# UAV2_0_DOC.net
KiCad netlist of a schematic drawn in Altium Designer
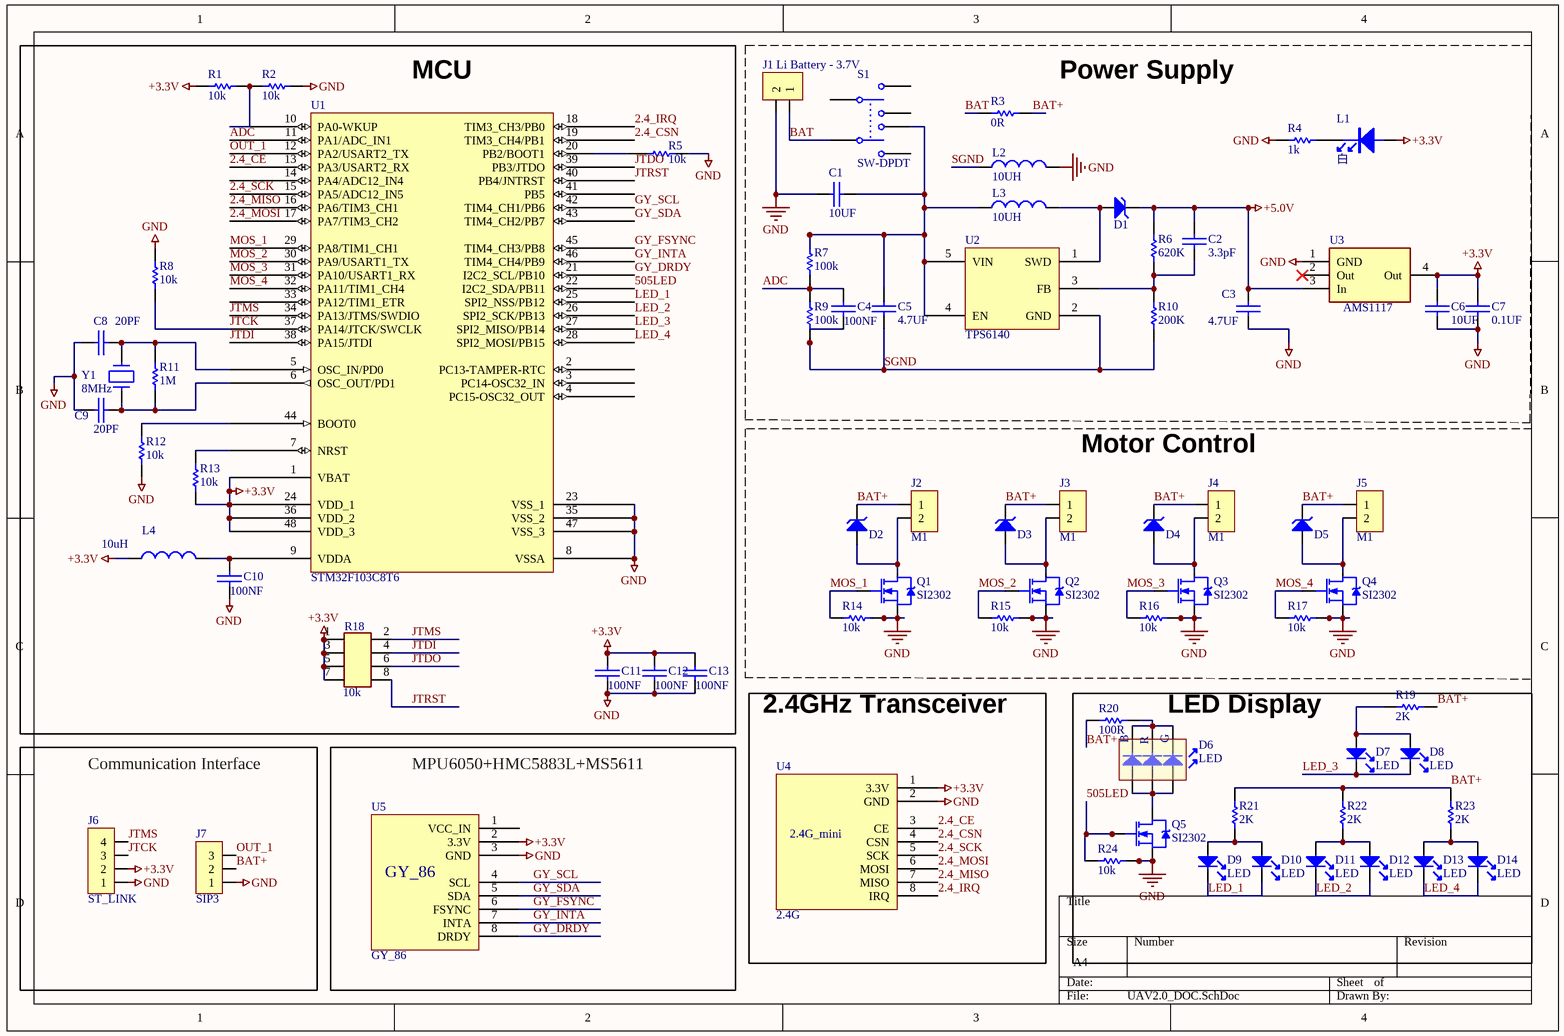
[diagram p0: UAV2.0_DOC.SchDoc]

(export (version "E")
  (design (tool "Eeschema 10.0.6"))
  (components
    (comp (ref "C1")
      (value "10UF")
      (footprint "1206C")
      (description "Capacitor/小容量电容")
      (libsource (lib "狗尾巴草设计室") (part "CAP"))
    )
    (comp (ref "C2")
      (value "3.3pF")
      (footprint "0805C")
      (description "Capacitor/小容量电容")
      (libsource (lib "狗尾巴草设计室") (part "CAP"))
    )
    (comp (ref "C3")
      (value "4.7UF")
      (footprint "1206C")
      (description "Capacitor/小容量电容")
      (libsource (lib "狗尾巴草设计室") (part "CAP"))
    )
    (comp (ref "C4")
      (value "100NF")
      (footprint "0805C")
      (description "Capacitor/小容量电容")
      (libsource (lib "狗尾巴草设计室") (part "CAP"))
    )
    (comp (ref "C5")
      (value "4.7UF")
      (footprint "0805C")
      (description "Capacitor/小容量电容")
      (libsource (lib "狗尾巴草设计室") (part "CAP"))
    )
    (comp (ref "C6")
      (value "10UF")
      (footprint "1206C")
      (description "Capacitor/小容量电容")
      (libsource (lib "狗尾巴草设计室") (part "CAP"))
    )
    (comp (ref "C7")
      (value "0.1UF")
      (footprint "0805C")
      (description "Capacitor/小容量电容")
      (libsource (lib "狗尾巴草设计室") (part "CAP"))
    )
    (comp (ref "C8")
      (value "20PF")
      (footprint "0805C")
      (description "Capacitor/小容量电容")
      (libsource (lib "狗尾巴草设计室") (part "CAP"))
    )
    (comp (ref "C9")
      (value "20PF")
      (footprint "0805C")
      (description "Capacitor/小容量电容")
      (libsource (lib "狗尾巴草设计室") (part "CAP"))
    )
    (comp (ref "C10")
      (value "100NF")
      (footprint "0805C")
      (description "Capacitor/小容量电容")
      (libsource (lib "狗尾巴草设计室") (part "CAP"))
    )
    (comp (ref "C11")
      (value "100NF")
      (footprint "0805C")
      (description "Capacitor/小容量电容")
      (libsource (lib "狗尾巴草设计室") (part "CAP"))
    )
    (comp (ref "C12")
      (value "100NF")
      (footprint "0805C")
      (description "Capacitor/小容量电容")
      (libsource (lib "狗尾巴草设计室") (part "CAP"))
    )
    (comp (ref "C13")
      (value "100NF")
      (footprint "0805C")
      (description "Capacitor/小容量电容")
      (libsource (lib "狗尾巴草设计室") (part "CAP"))
    )
    (comp (ref "D1")
      (value "DIODE-S")
      (footprint "C_SMA_3216")
      (description "SCHOTTKEY")
      (libsource (lib "狗尾巴草设计室") (part "DIODE-S"))
    )
    (comp (ref "D2")
      (value "DIODE-S")
      (footprint "C_SMA_3216")
      (description "SCHOTTKEY")
      (libsource (lib "狗尾巴草设计室") (part "DIODE-S"))
    )
    (comp (ref "D3")
      (value "DIODE-S")
      (footprint "C_SMA_3216")
      (description "SCHOTTKEY")
      (libsource (lib "狗尾巴草设计室") (part "DIODE-S"))
    )
    (comp (ref "D4")
      (value "DIODE-S")
      (footprint "C_SMA_3216")
      (description "SCHOTTKEY")
      (libsource (lib "狗尾巴草设计室") (part "DIODE-S"))
    )
    (comp (ref "D5")
      (value "DIODE-S")
      (footprint "C_SMA_3216")
      (description "SCHOTTKEY")
      (libsource (lib "狗尾巴草设计室") (part "DIODE-S"))
    )
    (comp (ref "D6") (value "LED") (footprint "LED5050_RGB") (libsource (lib "狗尾巴草设计室") (part "LED_5050RGB")))
    (comp (ref "D7") (value "LED") (footprint "0805D") (libsource (lib "狗尾巴草设计室") (part "LED")))
    (comp (ref "D8") (value "LED") (footprint "0805D") (libsource (lib "狗尾巴草设计室") (part "LED")))
    (comp (ref "D9") (value "LED") (footprint "0805D") (libsource (lib "狗尾巴草设计室") (part "LED")))
    (comp (ref "D10") (value "LED") (footprint "0805D") (libsource (lib "狗尾巴草设计室") (part "LED")))
    (comp (ref "D11") (value "LED") (footprint "0805D") (libsource (lib "狗尾巴草设计室") (part "LED")))
    (comp (ref "D12") (value "LED") (footprint "0805D") (libsource (lib "狗尾巴草设计室") (part "LED")))
    (comp (ref "D13") (value "LED") (footprint "0805D") (libsource (lib "狗尾巴草设计室") (part "LED")))
    (comp (ref "D14") (value "LED") (footprint "0805D") (libsource (lib "狗尾巴草设计室") (part "LED")))
    (comp (ref "J1")
      (value "Li Battery - 3.7V")
      (footprint "P2_2.0-2")
      (libsource (lib "狗尾巴草设计室") (part "SIP2"))
    )
    (comp (ref "J2") (value "M1") (footprint "P2_2.0-1") (libsource (lib "狗尾巴草设计室") (part "SIP2")))
    (comp (ref "J3") (value "M1") (footprint "P2_2.0-1") (libsource (lib "狗尾巴草设计室") (part "SIP2")))
    (comp (ref "J4") (value "M1") (footprint "P2_2.0-1") (libsource (lib "狗尾巴草设计室") (part "SIP2")))
    (comp (ref "J5") (value "M1") (footprint "P2_2.0-1") (libsource (lib "狗尾巴草设计室") (part "SIP2")))
    (comp (ref "J6") (value "ST_LINK") (footprint "P4_2.54-1") (libsource (lib "狗尾巴草设计室") (part "SIP4")))
    (comp (ref "J7") (value "SIP3") (footprint "PC_3") (libsource (lib "狗尾巴草设计室") (part "SIP3")))
    (comp (ref "L1") (value "白") (footprint "D0805") (libsource (lib "CommonSCH") (part "LED")))
    (comp (ref "L2") (value "10UH") (footprint "1206") (libsource (lib "狗尾巴草设计室") (part "L")))
    (comp (ref "L3") (value "10UH") (footprint "1206") (libsource (lib "狗尾巴草设计室") (part "L")))
    (comp (ref "L4")
      (value "INDUCTOR")
      (footprint "R0805")
      (fields (field (name "VAL") "10uH"))
      (libsource (lib "SCH") (part "INDUCTOR"))
    )
    (comp (ref "Q1")
      (value "SI2302")
      (footprint "PCB四轴lib_pcb:SI2302")
      (libsource (lib "BK四轴1.0_lib") (part "SI2302"))
    )
    (comp (ref "Q2")
      (value "SI2302")
      (footprint "PCB四轴lib_pcb:SI2302")
      (libsource (lib "BK四轴1.0_lib") (part "SI2302"))
    )
    (comp (ref "Q3")
      (value "SI2302")
      (footprint "PCB四轴lib_pcb:SI2302")
      (libsource (lib "BK四轴1.0_lib") (part "SI2302"))
    )
    (comp (ref "Q4")
      (value "SI2302")
      (footprint "PCB四轴lib_pcb:SI2302")
      (libsource (lib "BK四轴1.0_lib") (part "SI2302"))
    )
    (comp (ref "Q5")
      (value "SI2302")
      (footprint "PCB四轴lib_pcb:SI2302")
      (libsource (lib "BK四轴1.0_lib") (part "SI2302"))
    )
    (comp (ref "R1")
      (value "RES")
      (footprint "R0805")
      (description "Semiconductor Resistor")
      (fields (field (name "VAL") "10k") (field (name "PUBLISHER") "*"))
      (libsource (lib "SCH") (part "RES"))
    )
    (comp (ref "R2")
      (value "RES")
      (footprint "R0805")
      (description "Semiconductor Resistor")
      (fields (field (name "VAL") "10k") (field (name "PUBLISHER") "*"))
      (libsource (lib "SCH") (part "RES"))
    )
    (comp (ref "R3") (value "0R") (footprint "2512R - duplicate") (libsource (lib "狗尾巴草设计室") (part "Res_1")))
    (comp (ref "R4")
      (value "1k")
      (footprint "R0805")
      (description "Resistor")
      (fields (field (name "Comment") "Res1") (field (name "PUBLISHER") "Altium Limited"))
      (libsource (lib "SCHLIB1") (part "Res1"))
    )
    (comp (ref "R5")
      (value "RES")
      (footprint "R0805")
      (description "Semiconductor Resistor")
      (fields (field (name "VAL") "10k") (field (name "PUBLISHER") "*"))
      (libsource (lib "SCH") (part "RES"))
    )
    (comp (ref "R6") (value "620K") (footprint "0805R") (libsource (lib "狗尾巴草设计室") (part "Res")))
    (comp (ref "R7")
      (value "RES")
      (footprint "R0805")
      (description "Semiconductor Resistor")
      (fields (field (name "VAL") "100k") (field (name "PUBLISHER") "*"))
      (libsource (lib "SCH") (part "RES"))
    )
    (comp (ref "R8")
      (value "RES")
      (footprint "R0805")
      (description "Semiconductor Resistor")
      (fields (field (name "VAL") "10k") (field (name "PUBLISHER") "*"))
      (libsource (lib "SCH") (part "RES"))
    )
    (comp (ref "R9")
      (value "RES")
      (footprint "R0805")
      (description "Semiconductor Resistor")
      (fields (field (name "VAL") "100k") (field (name "PUBLISHER") "*"))
      (libsource (lib "SCH") (part "RES"))
    )
    (comp (ref "R10") (value "200K") (footprint "0805R") (libsource (lib "狗尾巴草设计室") (part "Res")))
    (comp (ref "R11")
      (value "RES")
      (footprint "R0805")
      (description "Semiconductor Resistor")
      (fields (field (name "VAL") "1M") (field (name "PUBLISHER") "*"))
      (libsource (lib "SCH") (part "RES"))
    )
    (comp (ref "R12")
      (value "RES")
      (footprint "R0805")
      (description "Semiconductor Resistor")
      (fields (field (name "VAL") "10k") (field (name "PUBLISHER") "*"))
      (libsource (lib "SCH") (part "RES"))
    )
    (comp (ref "R13")
      (value "RES")
      (footprint "R0805")
      (description "Semiconductor Resistor")
      (fields (field (name "VAL") "10k") (field (name "PUBLISHER") "*"))
      (libsource (lib "SCH") (part "RES"))
    )
    (comp (ref "R14")
      (value "RES")
      (footprint "R0805")
      (description "Semiconductor Resistor")
      (fields (field (name "VAL") "10k") (field (name "PUBLISHER") "*"))
      (libsource (lib "SCH") (part "RES"))
    )
    (comp (ref "R15")
      (value "RES")
      (footprint "R0805")
      (description "Semiconductor Resistor")
      (fields (field (name "VAL") "10k") (field (name "PUBLISHER") "*"))
      (libsource (lib "SCH") (part "RES"))
    )
    (comp (ref "R16")
      (value "RES")
      (footprint "R0805")
      (description "Semiconductor Resistor")
      (fields (field (name "VAL") "10k") (field (name "PUBLISHER") "*"))
      (libsource (lib "SCH") (part "RES"))
    )
    (comp (ref "R17")
      (value "RES")
      (footprint "R0805")
      (description "Semiconductor Resistor")
      (fields (field (name "VAL") "10k") (field (name "PUBLISHER") "*"))
      (libsource (lib "SCH") (part "RES"))
    )
    (comp (ref "R18")
      (value "10k")
      (footprint "8P4R_0603")
      (description "8P4R_0603")
      (libsource (lib "SCH") (part "8P4R_0603"))
    )
    (comp (ref "R19")
      (value "RES")
      (footprint "R0805")
      (description "Semiconductor Resistor")
      (fields (field (name "VAL") "2K") (field (name "PUBLISHER") "*"))
      (libsource (lib "SCH") (part "RES"))
    )
    (comp (ref "R20") (value "100R") (footprint "0805R") (libsource (lib "狗尾巴草设计室") (part "Res")))
    (comp (ref "R21")
      (value "RES")
      (footprint "R0805")
      (description "Semiconductor Resistor")
      (fields (field (name "VAL") "2K") (field (name "PUBLISHER") "*"))
      (libsource (lib "SCH") (part "RES"))
    )
    (comp (ref "R22")
      (value "RES")
      (footprint "R0805")
      (description "Semiconductor Resistor")
      (fields (field (name "VAL") "2K") (field (name "PUBLISHER") "*"))
      (libsource (lib "SCH") (part "RES"))
    )
    (comp (ref "R23")
      (value "RES")
      (footprint "R0805")
      (description "Semiconductor Resistor")
      (fields (field (name "VAL") "2K") (field (name "PUBLISHER") "*"))
      (libsource (lib "SCH") (part "RES"))
    )
    (comp (ref "R24")
      (value "RES")
      (footprint "R0805")
      (description "Semiconductor Resistor")
      (fields (field (name "VAL") "10k") (field (name "PUBLISHER") "*"))
      (libsource (lib "SCH") (part "RES"))
    )
    (comp (ref "S1")
      (value "SW-DPDT")
      (footprint "KEY_KFT7.0")
      (description "Double-Pole, Double-Throw Switch")
      (fields (field (name "PUBLISHER") "Altium Limited"))
      (libsource (lib "Miscellaneous Devices") (part "SW-DPDT"))
    )
    (comp (ref "U1")
      (value "STM32F103C8T6")
      (footprint "LQFP48_N")
      (description "STM32 ARM-based 32-bit MCU with 64 Kbytes Flash, 48-pin LQFP, Industrial Temperature")
      (fields (field (name "PUBLISHER") "*"))
      (libsource (lib "ZF_library") (part "STM32F103C8T6"))
    )
    (comp (ref "U2")
      (value "TPS6140")
      (footprint "SOT-23-5")
      (libsource (lib "BK四轴1.0_lib") (part "TPS6140"))
    )
    (comp (ref "U3")
      (value "AMS1117")
      (footprint "ZZ311")
      (description "Header, 2-Pin")
      (fields (field (name "PUBLISHER") "*"))
      (libsource (lib "CommonSCH") (part "AMS1117"))
    )
    (comp (ref "U4")
      (value "2.4G")
      (footprint "2.4G_mini")
      (libsource (lib "BK四轴1.0_lib") (part "2.4G_mini"))
    )
    (comp (ref "U5") (value "GY_86") (footprint "P8_2.54-1") (libsource (lib "BK四轴1.0_lib") (part "GY_86")))
    (comp (ref "Y1")
      (value "CRYSTAL1")
      (footprint "Y2")
      (fields (field (name "VAL") "8MHz"))
      (libsource (lib "SCH") (part "CRYSTAL1"))
    )
  )
  (nets
    (net (code "1") (name "+3.3V") (class "Default")
      (node (ref "C11") (pin "1") (pinfunction "1_1") (pintype "passive"))
      (node (ref "C12") (pin "1") (pinfunction "1_1") (pintype "passive"))
      (node (ref "C13") (pin "1") (pinfunction "1_1") (pintype "passive"))
      (node (ref "C6") (pin "1") (pinfunction "1_1") (pintype "passive"))
      (node (ref "C7") (pin "1") (pinfunction "1_1") (pintype "passive"))
      (node (ref "J6") (pin "2") (pinfunction "2_2") (pintype "passive"))
      (node (ref "L1") (pin "1") (pintype "passive"))
      (node (ref "L4") (pin "1") (pinfunction "1_1") (pintype "passive"))
      (node (ref "R1") (pin "2") (pinfunction "2_2") (pintype "passive"))
      (node (ref "R13") (pin "1") (pinfunction "1_1") (pintype "passive"))
      (node (ref "R18") (pin "1") (pinfunction "P_1") (pintype "passive"))
      (node (ref "R18") (pin "3") (pinfunction "P_3") (pintype "passive"))
      (node (ref "R18") (pin "5") (pinfunction "P_5") (pintype "passive"))
      (node (ref "R18") (pin "7") (pinfunction "P_7") (pintype "passive"))
      (node (ref "U1") (pin "1") (pinfunction "VBAT_1") (pintype "power_in"))
      (node (ref "U1") (pin "24") (pinfunction "VDD_1_24") (pintype "power_in"))
      (node (ref "U1") (pin "36") (pinfunction "VDD_2_36") (pintype "power_in"))
      (node (ref "U1") (pin "48") (pinfunction "VDD_3_48") (pintype "power_in"))
      (node (ref "U3") (pin "4") (pinfunction "Out_4") (pintype "passive"))
      (node (ref "U4") (pin "1") (pinfunction "3.3V_1") (pintype "passive"))
      (node (ref "U5") (pin "2") (pinfunction "3.3V_2") (pintype "passive"))
    )
    (net (code "2") (name "+5.0V") (class "Default")
      (node (ref "C2") (pin "1") (pinfunction "1_1") (pintype "passive"))
      (node (ref "C3") (pin "1") (pinfunction "1_1") (pintype "passive"))
      (node (ref "D1") (pin "2") (pintype "passive"))
      (node (ref "R6") (pin "2") (pinfunction "2_2") (pintype "passive"))
      (node (ref "U3") (pin "3") (pinfunction "In_3") (pintype "passive"))
    )
    (net (code "3") (name "/2.4_CE") (class "Default")
      (node (ref "U1") (pin "13") (pinfunction "PA3/USART2_RX_13") (pintype "bidirectional"))
      (node (ref "U4") (pin "3") (pinfunction "CE_3") (pintype "passive"))
    )
    (net (code "4") (name "/2.4_CSN") (class "Default")
      (node (ref "U1") (pin "19") (pinfunction "TIM3_CH4/PB1_19") (pintype "bidirectional"))
      (node (ref "U4") (pin "4") (pinfunction "CSN_4") (pintype "passive"))
    )
    (net (code "5") (name "/2.4_IRQ") (class "Default")
      (node (ref "U1") (pin "18") (pinfunction "TIM3_CH3/PB0_18") (pintype "bidirectional"))
      (node (ref "U4") (pin "8") (pinfunction "IRQ_8") (pintype "passive"))
    )
    (net (code "6") (name "/2.4_MISO") (class "Default")
      (node (ref "U1") (pin "16") (pinfunction "PA6/TIM3_CH1_16") (pintype "bidirectional"))
      (node (ref "U4") (pin "7") (pinfunction "MISO_7") (pintype "passive"))
    )
    (net (code "7") (name "/2.4_MOSI") (class "Default")
      (node (ref "U1") (pin "17") (pinfunction "PA7/TIM3_CH2_17") (pintype "bidirectional"))
      (node (ref "U4") (pin "6") (pinfunction "MOSI_6") (pintype "passive"))
    )
    (net (code "8") (name "/2.4_SCK") (class "Default")
      (node (ref "U1") (pin "15") (pinfunction "PA5/ADC12_IN5_15") (pintype "bidirectional"))
      (node (ref "U4") (pin "5") (pinfunction "SCK_5") (pintype "passive"))
    )
    (net (code "9") (name "/505LED") (class "Default")
      (node (ref "Q5") (pin "1") (pinfunction "G_1") (pintype "passive"))
      (node (ref "R24") (pin "2") (pinfunction "2_2") (pintype "passive"))
      (node (ref "U1") (pin "22") (pinfunction "I2C2_SDA/PB11_22") (pintype "bidirectional"))
    )
    (net (code "10") (name "/ADC") (class "Default")
      (node (ref "C4") (pin "1") (pinfunction "1_1") (pintype "passive"))
      (node (ref "R7") (pin "2") (pinfunction "2_2") (pintype "passive"))
      (node (ref "R9") (pin "1") (pinfunction "1_1") (pintype "passive"))
      (node (ref "U1") (pin "11") (pinfunction "PA1/ADC_IN1_11") (pintype "bidirectional"))
    )
    (net (code "11") (name "/BAT") (class "Default")
      (node (ref "J1") (pin "1") (pinfunction "1_1") (pintype "passive"))
      (node (ref "R3") (pin "1") (pinfunction "1_1") (pintype "passive"))
      (node (ref "S1") (pin "4") (pinfunction "4_4") (pintype "passive"))
    )
    (net (code "12") (name "/BAT+") (class "Default")
      (node (ref "D2") (pin "2") (pintype "passive"))
      (node (ref "D3") (pin "2") (pintype "passive"))
      (node (ref "D4") (pin "2") (pintype "passive"))
      (node (ref "D5") (pin "2") (pintype "passive"))
      (node (ref "J2") (pin "1") (pinfunction "1_1") (pintype "passive"))
      (node (ref "J3") (pin "1") (pinfunction "1_1") (pintype "passive"))
      (node (ref "J4") (pin "1") (pinfunction "1_1") (pintype "passive"))
      (node (ref "J5") (pin "1") (pinfunction "1_1") (pintype "passive"))
      (node (ref "J7") (pin "2") (pinfunction "2_2") (pintype "passive"))
      (node (ref "R19") (pin "2") (pinfunction "2_2") (pintype "passive"))
      (node (ref "R20") (pin "1") (pinfunction "1_1") (pintype "passive"))
      (node (ref "R21") (pin "1") (pinfunction "1_1") (pintype "passive"))
      (node (ref "R22") (pin "1") (pinfunction "1_1") (pintype "passive"))
      (node (ref "R23") (pin "1") (pinfunction "1_1") (pintype "passive"))
      (node (ref "R3") (pin "2") (pinfunction "2_2") (pintype "passive"))
    )
    (net (code "13") (name "/GY_DRDY") (class "Default")
      (node (ref "U1") (pin "21") (pinfunction "I2C2_SCL/PB10_21") (pintype "bidirectional"))
      (node (ref "U5") (pin "8") (pinfunction "DRDY_8") (pintype "passive"))
    )
    (net (code "14") (name "/GY_FSYNC") (class "Default")
      (node (ref "U1") (pin "45") (pinfunction "TIM4_CH3/PB8_45") (pintype "bidirectional"))
      (node (ref "U5") (pin "6") (pinfunction "FSYNC_6") (pintype "passive"))
    )
    (net (code "15") (name "/GY_INTA") (class "Default")
      (node (ref "U1") (pin "46") (pinfunction "TIM4_CH4/PB9_46") (pintype "bidirectional"))
      (node (ref "U5") (pin "7") (pinfunction "INTA_7") (pintype "passive"))
    )
    (net (code "16") (name "/GY_SCL") (class "Default")
      (node (ref "U1") (pin "42") (pinfunction "TIM4_CH1/PB6_42") (pintype "bidirectional"))
      (node (ref "U5") (pin "4") (pinfunction "SCL_4") (pintype "passive"))
    )
    (net (code "17") (name "/GY_SDA") (class "Default")
      (node (ref "U1") (pin "43") (pinfunction "TIM4_CH2/PB7_43") (pintype "bidirectional"))
      (node (ref "U5") (pin "5") (pinfunction "SDA_5") (pintype "passive"))
    )
    (net (code "18") (name "/JTCK") (class "Default")
      (node (ref "J6") (pin "3") (pinfunction "3_3") (pintype "passive"))
      (node (ref "R8") (pin "1") (pinfunction "1_1") (pintype "passive"))
      (node (ref "U1") (pin "37") (pinfunction "PA14/JTCK/SWCLK_37") (pintype "bidirectional"))
    )
    (net (code "19") (name "/JTDI") (class "Default")
      (node (ref "R18") (pin "4") (pinfunction "P_4") (pintype "passive"))
      (node (ref "U1") (pin "38") (pinfunction "PA15/JTDI_38") (pintype "bidirectional"))
    )
    (net (code "20") (name "/JTDO") (class "Default")
      (node (ref "R18") (pin "6") (pinfunction "P_6") (pintype "passive"))
      (node (ref "U1") (pin "39") (pinfunction "PB3/JTDO_39") (pintype "bidirectional"))
    )
    (net (code "21") (name "/JTMS") (class "Default")
      (node (ref "J6") (pin "4") (pinfunction "4_4") (pintype "passive"))
      (node (ref "R18") (pin "2") (pinfunction "P_2") (pintype "passive"))
      (node (ref "U1") (pin "34") (pinfunction "PA13/JTMS/SWDIO_34") (pintype "bidirectional"))
    )
    (net (code "22") (name "/JTRST") (class "Default")
      (node (ref "R18") (pin "8") (pinfunction "P_8") (pintype "passive"))
      (node (ref "U1") (pin "40") (pinfunction "PB4/JNTRST_40") (pintype "bidirectional"))
    )
    (net (code "23") (name "/LED_1") (class "Default")
      (node (ref "D10") (pin "2") (pinfunction "2_2") (pintype "passive"))
      (node (ref "D9") (pin "2") (pinfunction "2_2") (pintype "passive"))
      (node (ref "U1") (pin "25") (pinfunction "SPI2_NSS/PB12_25") (pintype "bidirectional"))
    )
    (net (code "24") (name "/LED_2") (class "Default")
      (node (ref "D11") (pin "2") (pinfunction "2_2") (pintype "passive"))
      (node (ref "D12") (pin "2") (pinfunction "2_2") (pintype "passive"))
      (node (ref "U1") (pin "26") (pinfunction "SPI2_SCK/PB13_26") (pintype "bidirectional"))
    )
    (net (code "25") (name "/LED_3") (class "Default")
      (node (ref "D7") (pin "2") (pinfunction "2_2") (pintype "passive"))
      (node (ref "D8") (pin "2") (pinfunction "2_2") (pintype "passive"))
      (node (ref "U1") (pin "27") (pinfunction "SPI2_MISO/PB14_27") (pintype "bidirectional"))
    )
    (net (code "26") (name "/LED_4") (class "Default")
      (node (ref "D13") (pin "2") (pinfunction "2_2") (pintype "passive"))
      (node (ref "D14") (pin "2") (pinfunction "2_2") (pintype "passive"))
      (node (ref "U1") (pin "28") (pinfunction "SPI2_MOSI/PB15_28") (pintype "bidirectional"))
    )
    (net (code "27") (name "/MOS_1") (class "Default")
      (node (ref "Q1") (pin "1") (pinfunction "G_1") (pintype "passive"))
      (node (ref "R14") (pin "2") (pinfunction "2_2") (pintype "passive"))
      (node (ref "U1") (pin "29") (pinfunction "PA8/TIM1_CH1_29") (pintype "bidirectional"))
    )
    (net (code "28") (name "/MOS_2") (class "Default")
      (node (ref "Q2") (pin "1") (pinfunction "G_1") (pintype "passive"))
      (node (ref "R15") (pin "2") (pinfunction "2_2") (pintype "passive"))
      (node (ref "U1") (pin "30") (pinfunction "PA9/USART1_TX_30") (pintype "bidirectional"))
    )
    (net (code "29") (name "/MOS_3") (class "Default")
      (node (ref "Q3") (pin "1") (pinfunction "G_1") (pintype "passive"))
      (node (ref "R16") (pin "2") (pinfunction "2_2") (pintype "passive"))
      (node (ref "U1") (pin "31") (pinfunction "PA10/USART1_RX_31") (pintype "bidirectional"))
    )
    (net (code "30") (name "/MOS_4") (class "Default")
      (node (ref "Q4") (pin "1") (pinfunction "G_1") (pintype "passive"))
      (node (ref "R17") (pin "2") (pinfunction "2_2") (pintype "passive"))
      (node (ref "U1") (pin "32") (pinfunction "PA11/TIM1_CH4_32") (pintype "bidirectional"))
    )
    (net (code "31") (name "/OUT_1") (class "Default")
      (node (ref "J7") (pin "3") (pinfunction "3_3") (pintype "passive"))
      (node (ref "U1") (pin "12") (pinfunction "PA2/USART2_TX_12") (pintype "bidirectional"))
    )
    (net (code "32") (name "/SGND") (class "Default")
      (node (ref "C4") (pin "2") (pinfunction "2_2") (pintype "passive"))
      (node (ref "C5") (pin "2") (pinfunction "2_2") (pintype "passive"))
      (node (ref "L2") (pin "2") (pinfunction "2_2") (pintype "passive"))
      (node (ref "R10") (pin "1") (pinfunction "1_1") (pintype "passive"))
      (node (ref "R9") (pin "2") (pinfunction "2_2") (pintype "passive"))
      (node (ref "U2") (pin "2") (pinfunction "GND_2") (pintype "passive"))
    )
    (net (code "33") (name "GND") (class "Default")
      (node (ref "C1") (pin "1") (pinfunction "1_1") (pintype "passive"))
      (node (ref "C10") (pin "2") (pinfunction "2_2") (pintype "passive"))
      (node (ref "C11") (pin "2") (pinfunction "2_2") (pintype "passive"))
      (node (ref "C12") (pin "2") (pinfunction "2_2") (pintype "passive"))
      (node (ref "C13") (pin "2") (pinfunction "2_2") (pintype "passive"))
      (node (ref "C3") (pin "2") (pinfunction "2_2") (pintype "passive"))
      (node (ref "C6") (pin "2") (pinfunction "2_2") (pintype "passive"))
      (node (ref "C7") (pin "2") (pinfunction "2_2") (pintype "passive"))
      (node (ref "C8") (pin "1") (pinfunction "1_1") (pintype "passive"))
      (node (ref "C9") (pin "1") (pinfunction "1_1") (pintype "passive"))
      (node (ref "J1") (pin "2") (pinfunction "2_2") (pintype "passive"))
      (node (ref "J6") (pin "1") (pinfunction "1_1") (pintype "passive"))
      (node (ref "J7") (pin "1") (pinfunction "1_1") (pintype "passive"))
      (node (ref "L2") (pin "1") (pinfunction "1_1") (pintype "passive"))
      (node (ref "Q1") (pin "2") (pinfunction "S_2") (pintype "passive"))
      (node (ref "Q2") (pin "2") (pinfunction "S_2") (pintype "passive"))
      (node (ref "Q3") (pin "2") (pinfunction "S_2") (pintype "passive"))
      (node (ref "Q4") (pin "2") (pinfunction "S_2") (pintype "passive"))
      (node (ref "Q5") (pin "2") (pinfunction "S_2") (pintype "passive"))
      (node (ref "R12") (pin "1") (pinfunction "1_1") (pintype "passive"))
      (node (ref "R14") (pin "1") (pinfunction "1_1") (pintype "passive"))
      (node (ref "R15") (pin "1") (pinfunction "1_1") (pintype "passive"))
      (node (ref "R16") (pin "1") (pinfunction "1_1") (pintype "passive"))
      (node (ref "R17") (pin "1") (pinfunction "1_1") (pintype "passive"))
      (node (ref "R2") (pin "1") (pinfunction "1_1") (pintype "passive"))
      (node (ref "R24") (pin "1") (pinfunction "1_1") (pintype "passive"))
      (node (ref "R4") (pin "2") (pinfunction "2_2") (pintype "passive"))
      (node (ref "R5") (pin "2") (pinfunction "2_2") (pintype "passive"))
      (node (ref "R8") (pin "2") (pinfunction "2_2") (pintype "passive"))
      (node (ref "U1") (pin "23") (pinfunction "VSS_1_23") (pintype "power_in"))
      (node (ref "U1") (pin "35") (pinfunction "VSS_2_35") (pintype "power_in"))
      (node (ref "U1") (pin "47") (pinfunction "VSS_3_47") (pintype "power_in"))
      (node (ref "U1") (pin "8") (pinfunction "VSSA_8") (pintype "power_in"))
      (node (ref "U3") (pin "1") (pinfunction "GND_1") (pintype "passive"))
      (node (ref "U4") (pin "2") (pinfunction "GND_2") (pintype "passive"))
      (node (ref "U5") (pin "3") (pinfunction "GND_3") (pintype "passive"))
    )
    (net (code "34") (name "Net-(D6-Pad1)") (class "Default")
      (node (ref "D6") (pin "1") (pinfunction "1_1") (pintype "passive"))
      (node (ref "D6") (pin "2") (pinfunction "2_2") (pintype "passive"))
      (node (ref "D6") (pin "3") (pinfunction "3_3") (pintype "passive"))
      (node (ref "R20") (pin "2") (pinfunction "2_2") (pintype "passive"))
    )
    (net (code "35") (name "Net-(D7-Pad1)") (class "Default")
      (node (ref "D7") (pin "1") (pinfunction "1_1") (pintype "passive"))
      (node (ref "D8") (pin "1") (pinfunction "1_1") (pintype "passive"))
      (node (ref "R19") (pin "1") (pinfunction "1_1") (pintype "passive"))
    )
    (net (code "36") (name "Net-(D10-Pad1)") (class "Default")
      (node (ref "D10") (pin "1") (pinfunction "1_1") (pintype "passive"))
      (node (ref "D9") (pin "1") (pinfunction "1_1") (pintype "passive"))
      (node (ref "R21") (pin "2") (pinfunction "2_2") (pintype "passive"))
    )
    (net (code "37") (name "Net-(D11-Pad1)") (class "Default")
      (node (ref "D11") (pin "1") (pinfunction "1_1") (pintype "passive"))
      (node (ref "D12") (pin "1") (pinfunction "1_1") (pintype "passive"))
      (node (ref "R22") (pin "2") (pinfunction "2_2") (pintype "passive"))
    )
    (net (code "38") (name "Net-(D13-Pad1)") (class "Default")
      (node (ref "D13") (pin "1") (pinfunction "1_1") (pintype "passive"))
      (node (ref "D14") (pin "1") (pinfunction "1_1") (pintype "passive"))
      (node (ref "R23") (pin "2") (pinfunction "2_2") (pintype "passive"))
    )
    (net (code "39") (name "Net-(L1-Pad2)") (class "Default")
      (node (ref "L1") (pin "2") (pintype "passive"))
      (node (ref "R4") (pin "1") (pinfunction "1_1") (pintype "passive"))
    )
    (net (code "40") (name "Net-(Q1-D)") (class "Default")
      (node (ref "D2") (pin "1") (pintype "passive"))
      (node (ref "J2") (pin "2") (pinfunction "2_2") (pintype "passive"))
      (node (ref "Q1") (pin "3") (pinfunction "D_3") (pintype "passive"))
    )
    (net (code "41") (name "Net-(Q2-D)") (class "Default")
      (node (ref "D3") (pin "1") (pintype "passive"))
      (node (ref "J3") (pin "2") (pinfunction "2_2") (pintype "passive"))
      (node (ref "Q2") (pin "3") (pinfunction "D_3") (pintype "passive"))
    )
    (net (code "42") (name "Net-(Q3-D)") (class "Default")
      (node (ref "D4") (pin "1") (pintype "passive"))
      (node (ref "J4") (pin "2") (pinfunction "2_2") (pintype "passive"))
      (node (ref "Q3") (pin "3") (pinfunction "D_3") (pintype "passive"))
    )
    (net (code "43") (name "Net-(Q4-D)") (class "Default")
      (node (ref "D5") (pin "1") (pintype "passive"))
      (node (ref "J5") (pin "2") (pinfunction "2_2") (pintype "passive"))
      (node (ref "Q4") (pin "3") (pinfunction "D_3") (pintype "passive"))
    )
    (net (code "44") (name "Net-(Q5-D)") (class "Default")
      (node (ref "D6") (pin "4") (pinfunction "4_4") (pintype "passive"))
      (node (ref "D6") (pin "5") (pinfunction "5_5") (pintype "passive"))
      (node (ref "D6") (pin "6") (pinfunction "6_6") (pintype "passive"))
      (node (ref "Q5") (pin "3") (pinfunction "D_3") (pintype "passive"))
    )
    (net (code "45") (name "Net-(U1-BOOT0)") (class "Default")
      (node (ref "R12") (pin "2") (pinfunction "2_2") (pintype "passive"))
      (node (ref "U1") (pin "44") (pinfunction "BOOT0_44") (pintype "input"))
    )
    (net (code "46") (name "Net-(U1-NRST)") (class "Default")
      (node (ref "R13") (pin "2") (pinfunction "2_2") (pintype "passive"))
      (node (ref "U1") (pin "7") (pinfunction "NRST_7") (pintype "bidirectional"))
    )
    (net (code "47") (name "Net-(U1-OSC_IN{slash}PD0)") (class "Default")
      (node (ref "C8") (pin "2") (pinfunction "2_2") (pintype "passive"))
      (node (ref "R11") (pin "2") (pinfunction "2_2") (pintype "passive"))
      (node (ref "U1") (pin "5") (pinfunction "OSC_IN/PD0_5") (pintype "input"))
      (node (ref "Y1") (pin "2") (pinfunction "2_2") (pintype "passive"))
    )
    (net (code "48") (name "Net-(U1-OSC_OUT{slash}PD1)") (class "Default")
      (node (ref "C9") (pin "2") (pinfunction "2_2") (pintype "passive"))
      (node (ref "R11") (pin "1") (pinfunction "1_1") (pintype "passive"))
      (node (ref "U1") (pin "6") (pinfunction "OSC_OUT/PD1_6") (pintype "output"))
      (node (ref "Y1") (pin "1") (pinfunction "1_1") (pintype "passive"))
    )
    (net (code "49") (name "Net-(U1-PA0-WKUP)") (class "Default")
      (node (ref "R1") (pin "1") (pinfunction "1_1") (pintype "passive"))
      (node (ref "R2") (pin "2") (pinfunction "2_2") (pintype "passive"))
      (node (ref "U1") (pin "10") (pinfunction "PA0-WKUP_10") (pintype "bidirectional"))
    )
    (net (code "50") (name "Net-(U1-PB2{slash}BOOT1)") (class "Default")
      (node (ref "R5") (pin "1") (pinfunction "1_1") (pintype "passive"))
      (node (ref "U1") (pin "20") (pinfunction "PB2/BOOT1_20") (pintype "bidirectional"))
    )
    (net (code "51") (name "Net-(U1-VDDA)") (class "Default")
      (node (ref "C10") (pin "1") (pinfunction "1_1") (pintype "passive"))
      (node (ref "L4") (pin "2") (pinfunction "2_2") (pintype "passive"))
      (node (ref "U1") (pin "9") (pinfunction "VDDA_9") (pintype "power_in"))
    )
    (net (code "52") (name "Net-(U2-EN)") (class "Default")
      (node (ref "C1") (pin "2") (pinfunction "2_2") (pintype "passive"))
      (node (ref "C5") (pin "1") (pinfunction "1_1") (pintype "passive"))
      (node (ref "L3") (pin "2") (pinfunction "2_2") (pintype "passive"))
      (node (ref "R7") (pin "1") (pinfunction "1_1") (pintype "passive"))
      (node (ref "S1") (pin "5") (pinfunction "5_5") (pintype "passive"))
      (node (ref "U2") (pin "4") (pinfunction "EN_4") (pintype "passive"))
      (node (ref "U2") (pin "5") (pinfunction "VIN_5") (pintype "passive"))
    )
    (net (code "53") (name "Net-(U2-FB)") (class "Default")
      (node (ref "C2") (pin "2") (pinfunction "2_2") (pintype "passive"))
      (node (ref "R10") (pin "2") (pinfunction "2_2") (pintype "passive"))
      (node (ref "R6") (pin "1") (pinfunction "1_1") (pintype "passive"))
      (node (ref "U2") (pin "3") (pinfunction "FB_3") (pintype "passive"))
    )
    (net (code "54") (name "Net-(U2-SWD)") (class "Default")
      (node (ref "D1") (pin "1") (pintype "passive"))
      (node (ref "L3") (pin "1") (pinfunction "1_1") (pintype "passive"))
      (node (ref "U2") (pin "1") (pinfunction "SWD_1") (pintype "passive"))
    )
    (net (code "55") (name "unconnected-(S1-Pad1)") (class "Default")
      (node (ref "S1") (pin "1") (pinfunction "1_1") (pintype "passive"))
    )
    (net (code "56") (name "unconnected-(S1-Pad2)") (class "Default")
      (node (ref "S1") (pin "2") (pinfunction "2_2") (pintype "passive"))
    )
    (net (code "57") (name "unconnected-(S1-Pad3)") (class "Default")
      (node (ref "S1") (pin "3") (pinfunction "3_3") (pintype "passive"))
    )
    (net (code "58") (name "unconnected-(S1-Pad6)") (class "Default")
      (node (ref "S1") (pin "6") (pinfunction "6_6") (pintype "passive"))
    )
    (net (code "59") (name "unconnected-(U1-PA4{slash}ADC12_IN4-Pad14)") (class "Default")
      (node (ref "U1") (pin "14") (pinfunction "PA4/ADC12_IN4_14") (pintype "bidirectional"))
    )
    (net (code "60") (name "unconnected-(U1-PA12{slash}TIM1_ETR-Pad33)") (class "Default")
      (node (ref "U1") (pin "33") (pinfunction "PA12/TIM1_ETR_33") (pintype "bidirectional"))
    )
    (net (code "61") (name "unconnected-(U1-PB5-Pad41)") (class "Default")
      (node (ref "U1") (pin "41") (pinfunction "PB5_41") (pintype "bidirectional"))
    )
    (net (code "62") (name "unconnected-(U1-PC13-TAMPER-RTC-Pad2)") (class "Default")
      (node (ref "U1") (pin "2") (pinfunction "PC13-TAMPER-RTC_2") (pintype "bidirectional"))
    )
    (net (code "63") (name "unconnected-(U1-PC14-OSC32_IN-Pad3)") (class "Default")
      (node (ref "U1") (pin "3") (pinfunction "PC14-OSC32_IN_3") (pintype "bidirectional"))
    )
    (net (code "64") (name "unconnected-(U1-PC15-OSC32_OUT-Pad4)") (class "Default")
      (node (ref "U1") (pin "4") (pinfunction "PC15-OSC32_OUT_4") (pintype "bidirectional"))
    )
    (net (code "65") (name "unconnected-(U3-Out-Pad2)") (class "Default")
      (node (ref "U3") (pin "2") (pinfunction "Out_2") (pintype "passive+no_connect"))
    )
    (net (code "66") (name "unconnected-(U5-VCC_IN-Pad1)") (class "Default")
      (node (ref "U5") (pin "1") (pinfunction "VCC_IN_1") (pintype "passive"))
    )
  )
)
